# FT232-Breakout-v10.net
KiCad netlist of a schematic drawn in EAGLE
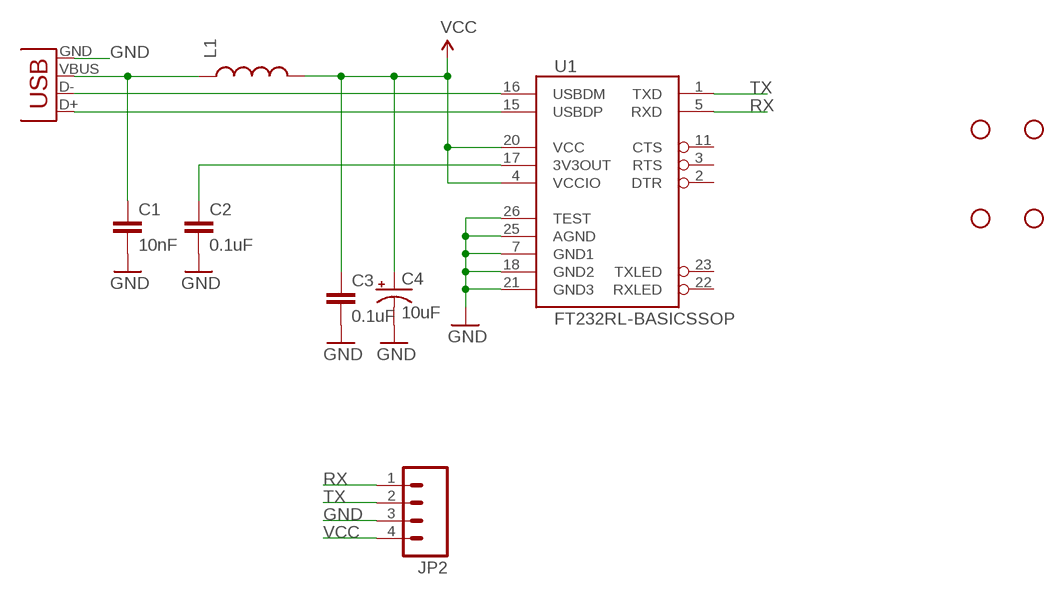
[diagram p0: schematic, sheet 1]

(export (version "E")
  (design (tool "Eeschema 10.0.6"))
  (components
    (comp (ref "C1")
      (value "10nF")
      (footprint "eagle-import:0603-CAP")
      (libsource (lib "eagle-import") (part "CAP0603-CAP"))
    )
    (comp (ref "C2")
      (value "0.1uF")
      (footprint "eagle-import:0603-CAP")
      (libsource (lib "eagle-import") (part "CAP0603-CAP"))
    )
    (comp (ref "C3")
      (value "0.1uF")
      (footprint "eagle-import:0603-CAP")
      (libsource (lib "eagle-import") (part "CAP0603-CAP"))
    )
    (comp (ref "C4")
      (value "10uF")
      (footprint "eagle-import:EIA3216")
      (libsource (lib "eagle-import") (part "CAP_POL1206"))
    )
    (comp (ref "JP1")
      (value "USB-B")
      (footprint "eagle-import:USB-B-PTH")
      (libsource (lib "eagle-import") (part "USBPTH"))
    )
    (comp (ref "JP2")
      (value "M04PTH")
      (footprint "eagle-import:1X04")
      (libsource (lib "eagle-import") (part "M04PTH"))
    )
    (comp (ref "L1")
      (value "INDUCTOR0603")
      (footprint "eagle-import:0603")
      (libsource (lib "eagle-import") (part "INDUCTOR0603"))
    )
    (comp (ref "STANDOFF1")
      (value "STAND-OFF")
      (footprint "eagle-import:STAND-OFF")
      (libsource (lib "eagle-import") (part "STAND-OFF"))
    )
    (comp (ref "STANDOFF2")
      (value "STAND-OFF")
      (footprint "eagle-import:STAND-OFF")
      (libsource (lib "eagle-import") (part "STAND-OFF"))
    )
    (comp (ref "STANDOFF3")
      (value "STAND-OFF")
      (footprint "eagle-import:STAND-OFF")
      (libsource (lib "eagle-import") (part "STAND-OFF"))
    )
    (comp (ref "STANDOFF4")
      (value "STAND-OFF")
      (footprint "eagle-import:STAND-OFF")
      (libsource (lib "eagle-import") (part "STAND-OFF"))
    )
    (comp (ref "U1")
      (value "FT232RL-BASICSSOP")
      (footprint "eagle-import:SSOP28DB")
      (libsource (lib "eagle-import") (part "FT232RL-BASICSSOP"))
    )
  )
  (nets
    (net (code "1") (name "/RX") (class "Default")
      (node (ref "JP2") (pin "1") (pinfunction "1_1") (pintype "passive"))
      (node (ref "U1") (pin "5") (pinfunction "RXD_5") (pintype "input"))
    )
    (net (code "2") (name "/TX") (class "Default")
      (node (ref "JP2") (pin "2") (pinfunction "2_2") (pintype "passive"))
      (node (ref "U1") (pin "1") (pinfunction "TXD_1") (pintype "output"))
    )
    (net (code "3") (name "GND") (class "Default")
      (node (ref "C1") (pin "2") (pinfunction "2_2") (pintype "passive"))
      (node (ref "C2") (pin "2") (pinfunction "2_2") (pintype "passive"))
      (node (ref "C3") (pin "2") (pinfunction "2_2") (pintype "passive"))
      (node (ref "C4") (pin "C") (pinfunction "-_C") (pintype "passive"))
      (node (ref "JP1") (pin "GND") (pinfunction "GND_GND") (pintype "bidirectional"))
      (node (ref "JP2") (pin "3") (pinfunction "3_3") (pintype "passive"))
      (node (ref "U1") (pin "18") (pinfunction "GND2_18") (pintype "power_in"))
      (node (ref "U1") (pin "21") (pinfunction "GND3_21") (pintype "power_in"))
      (node (ref "U1") (pin "25") (pinfunction "AGND_25") (pintype "power_in"))
      (node (ref "U1") (pin "26") (pinfunction "TEST_26") (pintype "input"))
      (node (ref "U1") (pin "7") (pinfunction "GND1_7") (pintype "power_in"))
    )
    (net (code "4") (name "Net-(C1-Pad1)") (class "Default")
      (node (ref "C1") (pin "1") (pinfunction "1_1") (pintype "passive"))
      (node (ref "JP1") (pin "VBUS") (pinfunction "VBUS_VBUS") (pintype "bidirectional"))
      (node (ref "L1") (pin "1") (pinfunction "1_1") (pintype "passive"))
    )
    (net (code "5") (name "Net-(U1-3V3OUT)") (class "Default")
      (node (ref "C2") (pin "1") (pinfunction "1_1") (pintype "passive"))
      (node (ref "U1") (pin "17") (pinfunction "3V3OUT_17") (pintype "output"))
    )
    (net (code "6") (name "Net-(U1-USBDM)") (class "Default")
      (node (ref "JP1") (pin "D-") (pinfunction "D-_D-") (pintype "bidirectional"))
      (node (ref "U1") (pin "16") (pinfunction "USBDM_16") (pintype "bidirectional"))
    )
    (net (code "7") (name "Net-(U1-USBDP)") (class "Default")
      (node (ref "JP1") (pin "D+") (pinfunction "D+_D+") (pintype "bidirectional"))
      (node (ref "U1") (pin "15") (pinfunction "USBDP_15") (pintype "bidirectional"))
    )
    (net (code "8") (name "VCC") (class "Default")
      (node (ref "C3") (pin "1") (pinfunction "1_1") (pintype "passive"))
      (node (ref "C4") (pin "A") (pinfunction "+_A") (pintype "passive"))
      (node (ref "JP2") (pin "4") (pinfunction "4_4") (pintype "passive"))
      (node (ref "L1") (pin "2") (pinfunction "2_2") (pintype "passive"))
      (node (ref "U1") (pin "20") (pinfunction "VCC_20") (pintype "power_in"))
      (node (ref "U1") (pin "4") (pinfunction "VCCIO_4") (pintype "power_in"))
    )
    (net (code "9") (name "unconnected-(U1-CTS-Pad11)") (class "Default")
      (node (ref "U1") (pin "11") (pinfunction "CTS_11") (pintype "bidirectional"))
    )
    (net (code "10") (name "unconnected-(U1-DTR-Pad2)") (class "Default")
      (node (ref "U1") (pin "2") (pinfunction "DTR_2") (pintype "bidirectional"))
    )
    (net (code "11") (name "unconnected-(U1-RTS-Pad3)") (class "Default")
      (node (ref "U1") (pin "3") (pinfunction "RTS_3") (pintype "bidirectional"))
    )
    (net (code "12") (name "unconnected-(U1-RXLED-Pad22)") (class "Default")
      (node (ref "U1") (pin "22") (pinfunction "RXLED_22") (pintype "bidirectional"))
    )
    (net (code "13") (name "unconnected-(U1-TXLED-Pad23)") (class "Default")
      (node (ref "U1") (pin "23") (pinfunction "TXLED_23") (pintype "bidirectional"))
    )
  )
)
